# cpu.net
KiCad netlist of a schematic drawn in Altium Designer
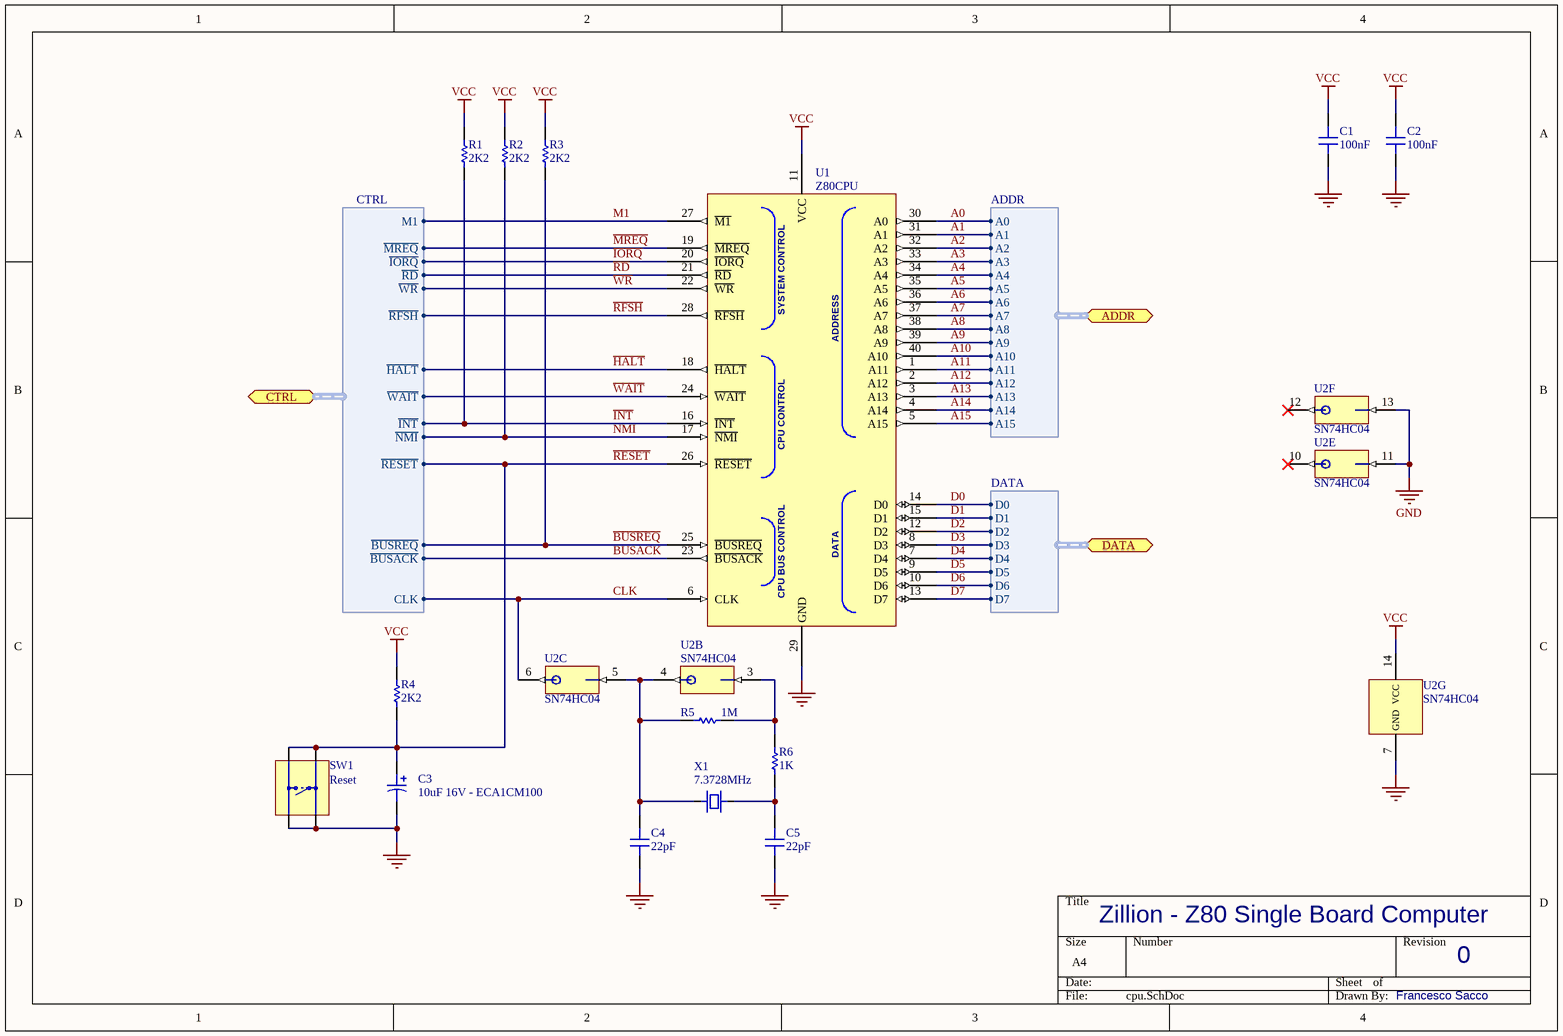
[diagram p0: cpu.SchDoc]

(export (version "E")
  (design (tool "Eeschema 10.0.6"))
  (components
    (comp (ref "C1")
      (value "100nF")
      (footprint "DiskCapacitor")
      (description "Capacitor")
      (libsource (lib "Basic") (part "Capacitor"))
    )
    (comp (ref "C2")
      (value "100nF")
      (footprint "DiskCapacitor")
      (description "Capacitor")
      (libsource (lib "Basic") (part "Capacitor"))
    )
    (comp (ref "C3")
      (value "10uF 16V - ECA1CM100")
      (footprint "ECA 5x11")
      (description "10uF 16V")
      (libsource (lib "Panasonic") (part "ECA1CM100"))
    )
    (comp (ref "C4")
      (value "22pF")
      (footprint "DiskCapacitor")
      (description "Capacitor")
      (libsource (lib "Basic") (part "Capacitor"))
    )
    (comp (ref "C5")
      (value "22pF")
      (footprint "DiskCapacitor")
      (description "Capacitor")
      (libsource (lib "Basic") (part "Capacitor"))
    )
    (comp (ref "R1") (value "2K2") (footprint "CR12") (libsource (lib "Basic") (part "Resistor")))
    (comp (ref "R2") (value "2K2") (footprint "CR12") (libsource (lib "Basic") (part "Resistor")))
    (comp (ref "R3") (value "2K2") (footprint "CR12") (libsource (lib "Basic") (part "Resistor")))
    (comp (ref "R4") (value "2K2") (footprint "CR12") (libsource (lib "Basic") (part "Resistor")))
    (comp (ref "R5")
      (value "1M")
      (footprint "CR12")
      (description "2K2")
      (libsource (lib "Basic") (part "Resistor"))
    )
    (comp (ref "R6")
      (value "1K")
      (footprint "CR12")
      (description "2K2")
      (libsource (lib "Basic") (part "Resistor"))
    )
    (comp (ref "SW1")
      (value "Reset")
      (footprint "EVQPAx09K")
      (description "5N Type Light Touch Switches")
      (libsource (lib "Panasonic") (part "EVQPA"))
    )
    (comp (ref "U1")
      (value "Z80CPU")
      (footprint "Z84C00xxPEG")
      (description "Z80 - CPU")
      (libsource (lib "Zilog") (part "Z84C00xxPEG"))
    )
    (comp (ref "U2")
      (value "SN74HC04")
      (footprint "CDIP14")
      (description "Hex Inverters")
      (libsource (lib "") (part "SN74HC04_1"))
    )
    (comp (ref "X1")
      (value "7.3728MHz")
      (footprint "HC49S")
      (description "Crystal HC49S")
      (libsource (lib "Basic") (part "HC49S"))
    )
  )
  (nets
    (net (code "4") (name "/A0") (class "Default")
      (node (ref "U1") (pin "30") (pinfunction "A0_30") (pintype "output"))
    )
    (net (code "5") (name "/A1") (class "Default")
      (node (ref "U1") (pin "31") (pinfunction "A1_31") (pintype "output"))
    )
    (net (code "6") (name "/A2") (class "Default")
      (node (ref "U1") (pin "32") (pinfunction "A2_32") (pintype "output"))
    )
    (net (code "7") (name "/A3") (class "Default")
      (node (ref "U1") (pin "33") (pinfunction "A3_33") (pintype "output"))
    )
    (net (code "8") (name "/A4") (class "Default")
      (node (ref "U1") (pin "34") (pinfunction "A4_34") (pintype "output"))
    )
    (net (code "9") (name "/A5") (class "Default")
      (node (ref "U1") (pin "35") (pinfunction "A5_35") (pintype "output"))
    )
    (net (code "10") (name "/A6") (class "Default")
      (node (ref "U1") (pin "36") (pinfunction "A6_36") (pintype "output"))
    )
    (net (code "11") (name "/A7") (class "Default")
      (node (ref "U1") (pin "37") (pinfunction "A7_37") (pintype "output"))
    )
    (net (code "12") (name "/A8") (class "Default")
      (node (ref "U1") (pin "38") (pinfunction "A8_38") (pintype "output"))
    )
    (net (code "13") (name "/A9") (class "Default")
      (node (ref "U1") (pin "39") (pinfunction "A9_39") (pintype "output"))
    )
    (net (code "14") (name "/A10") (class "Default")
      (node (ref "U1") (pin "40") (pinfunction "A10_40") (pintype "output"))
    )
    (net (code "15") (name "/A11") (class "Default")
      (node (ref "U1") (pin "1") (pinfunction "A11_1") (pintype "output"))
    )
    (net (code "16") (name "/A12") (class "Default")
      (node (ref "U1") (pin "2") (pinfunction "A12_2") (pintype "output"))
    )
    (net (code "17") (name "/A13") (class "Default")
      (node (ref "U1") (pin "3") (pinfunction "A13_3") (pintype "output"))
    )
    (net (code "18") (name "/A14") (class "Default")
      (node (ref "U1") (pin "4") (pinfunction "A14_4") (pintype "output"))
    )
    (net (code "19") (name "/A15") (class "Default")
      (node (ref "U1") (pin "5") (pinfunction "A15_5") (pintype "output"))
    )
    (net (code "20") (name "/CLK") (class "Default")
      (node (ref "U1") (pin "6") (pinfunction "CLK_6") (pintype "input"))
      (node (ref "U2") (pin "6") (pinfunction "Y_6") (pintype "output"))
    )
    (net (code "21") (name "/D0") (class "Default")
      (node (ref "U1") (pin "14") (pinfunction "D0_14") (pintype "bidirectional"))
    )
    (net (code "22") (name "/D1") (class "Default")
      (node (ref "U1") (pin "15") (pinfunction "D1_15") (pintype "bidirectional"))
    )
    (net (code "23") (name "/D2") (class "Default")
      (node (ref "U1") (pin "12") (pinfunction "D2_12") (pintype "bidirectional"))
    )
    (net (code "24") (name "/D3") (class "Default")
      (node (ref "U1") (pin "8") (pinfunction "D3_8") (pintype "bidirectional"))
    )
    (net (code "25") (name "/D4") (class "Default")
      (node (ref "U1") (pin "7") (pinfunction "D4_7") (pintype "bidirectional"))
    )
    (net (code "26") (name "/D5") (class "Default")
      (node (ref "U1") (pin "9") (pinfunction "D5_9") (pintype "bidirectional"))
    )
    (net (code "27") (name "/D6") (class "Default")
      (node (ref "U1") (pin "10") (pinfunction "D6_10") (pintype "bidirectional"))
    )
    (net (code "28") (name "/D7") (class "Default")
      (node (ref "U1") (pin "13") (pinfunction "D7_13") (pintype "bidirectional"))
    )
    (net (code "29") (name "/M1") (class "Default")
      (node (ref "U1") (pin "27") (pinfunction "~{M1}_27") (pintype "output"))
    )
    (net (code "33") (name "/~{BUSACK}") (class "Default")
      (node (ref "U1") (pin "23") (pinfunction "~{BUSACK}_23") (pintype "output"))
    )
    (net (code "34") (name "/~{BUSREQ}") (class "Default")
      (node (ref "R3") (pin "1") (pinfunction "1_1") (pintype "passive"))
      (node (ref "U1") (pin "25") (pinfunction "~{BUSREQ}_25") (pintype "input"))
    )
    (net (code "35") (name "/~{HALT}") (class "Default")
      (node (ref "U1") (pin "18") (pinfunction "~{HALT}_18") (pintype "output"))
    )
    (net (code "36") (name "/~{INT}") (class "Default")
      (node (ref "R1") (pin "1") (pinfunction "1_1") (pintype "passive"))
      (node (ref "U1") (pin "16") (pinfunction "~{INT}_16") (pintype "input"))
    )
    (net (code "37") (name "/~{IORQ}") (class "Default")
      (node (ref "U1") (pin "20") (pinfunction "~{IORQ}_20") (pintype "output"))
    )
    (net (code "38") (name "/~{MREQ}") (class "Default")
      (node (ref "U1") (pin "19") (pinfunction "~{MREQ}_19") (pintype "output"))
    )
    (net (code "39") (name "/~{NMI}") (class "Default")
      (node (ref "R2") (pin "1") (pinfunction "1_1") (pintype "passive"))
      (node (ref "U1") (pin "17") (pinfunction "~{NMI}_17") (pintype "input"))
    )
    (net (code "40") (name "/~{RD}") (class "Default")
      (node (ref "U1") (pin "21") (pinfunction "~{RD}_21") (pintype "output"))
    )
    (net (code "41") (name "/~{RESET}") (class "Default")
      (node (ref "C3") (pin "1") (pinfunction "1_1") (pintype "passive"))
      (node (ref "R4") (pin "1") (pinfunction "1_1") (pintype "passive"))
      (node (ref "SW1") (pin "3") (pinfunction "3_3") (pintype "power_in"))
      (node (ref "SW1") (pin "4") (pinfunction "4_4") (pintype "power_in"))
      (node (ref "U1") (pin "26") (pinfunction "~{RESET}_26") (pintype "input"))
    )
    (net (code "42") (name "/~{RFSH}") (class "Default")
      (node (ref "U1") (pin "28") (pinfunction "~{RFSH}_28") (pintype "output"))
    )
    (net (code "43") (name "/~{WAIT}") (class "Default")
      (node (ref "U1") (pin "24") (pinfunction "~{WAIT}_24") (pintype "input"))
    )
    (net (code "44") (name "/~{WR}") (class "Default")
      (node (ref "U1") (pin "22") (pinfunction "~{WR}_22") (pintype "output"))
    )
    (net (code "45") (name "GND") (class "Default")
      (node (ref "C1") (pin "1") (pinfunction "1_1") (pintype "passive"))
      (node (ref "C2") (pin "1") (pinfunction "1_1") (pintype "passive"))
      (node (ref "C3") (pin "2") (pinfunction "2_2") (pintype "passive"))
      (node (ref "C4") (pin "1") (pinfunction "1_1") (pintype "passive"))
      (node (ref "C5") (pin "1") (pinfunction "1_1") (pintype "passive"))
      (node (ref "SW1") (pin "1") (pinfunction "1_1") (pintype "power_in"))
      (node (ref "SW1") (pin "2") (pinfunction "2_2") (pintype "power_in"))
      (node (ref "U1") (pin "29") (pinfunction "GND_29") (pintype "power_in"))
      (node (ref "U2") (pin "11") (pinfunction "A_11") (pintype "input"))
      (node (ref "U2") (pin "13") (pinfunction "A_13") (pintype "input"))
      (node (ref "U2") (pin "7") (pinfunction "GND_7") (pintype "power_in"))
    )
    (net (code "46") (name "Net-(C5-Pad2)") (class "Default")
      (node (ref "C5") (pin "2") (pinfunction "2_2") (pintype "passive"))
      (node (ref "R6") (pin "1") (pinfunction "1_1") (pintype "passive"))
      (node (ref "X1") (pin "2") (pinfunction "2_2") (pintype "passive"))
    )
    (net (code "47") (name "Net-(U2B-A)") (class "Default")
      (node (ref "R5") (pin "1") (pinfunction "1_1") (pintype "passive"))
      (node (ref "R6") (pin "2") (pinfunction "2_2") (pintype "passive"))
      (node (ref "U2") (pin "3") (pinfunction "A_3") (pintype "input"))
    )
    (net (code "48") (name "Net-(U2B-Y)") (class "Default")
      (node (ref "C4") (pin "2") (pinfunction "2_2") (pintype "passive"))
      (node (ref "R5") (pin "2") (pinfunction "2_2") (pintype "passive"))
      (node (ref "U2") (pin "4") (pinfunction "Y_4") (pintype "output"))
      (node (ref "U2") (pin "5") (pinfunction "A_5") (pintype "input"))
      (node (ref "X1") (pin "1") (pinfunction "1_1") (pintype "passive"))
    )
    (net (code "49") (name "VCC") (class "Default")
      (node (ref "C1") (pin "2") (pinfunction "2_2") (pintype "passive"))
      (node (ref "C2") (pin "2") (pinfunction "2_2") (pintype "passive"))
      (node (ref "R1") (pin "2") (pinfunction "2_2") (pintype "passive"))
      (node (ref "R2") (pin "2") (pinfunction "2_2") (pintype "passive"))
      (node (ref "R3") (pin "2") (pinfunction "2_2") (pintype "passive"))
      (node (ref "R4") (pin "2") (pinfunction "2_2") (pintype "passive"))
      (node (ref "U1") (pin "11") (pinfunction "VCC_11") (pintype "power_in"))
      (node (ref "U2") (pin "14") (pinfunction "VCC_14") (pintype "power_in"))
    )
    (net (code "50") (name "unconnected-(U2E-Y-Pad10)") (class "Default")
      (node (ref "U2") (pin "10") (pinfunction "Y_10") (pintype "output+no_connect"))
    )
    (net (code "51") (name "unconnected-(U2F-Y-Pad12)") (class "Default")
      (node (ref "U2") (pin "12") (pinfunction "Y_12") (pintype "output+no_connect"))
    )
  )
)
